# SENSORS_FMU3_REV_G.net
KiCad netlist of a schematic drawn in Altium Designer
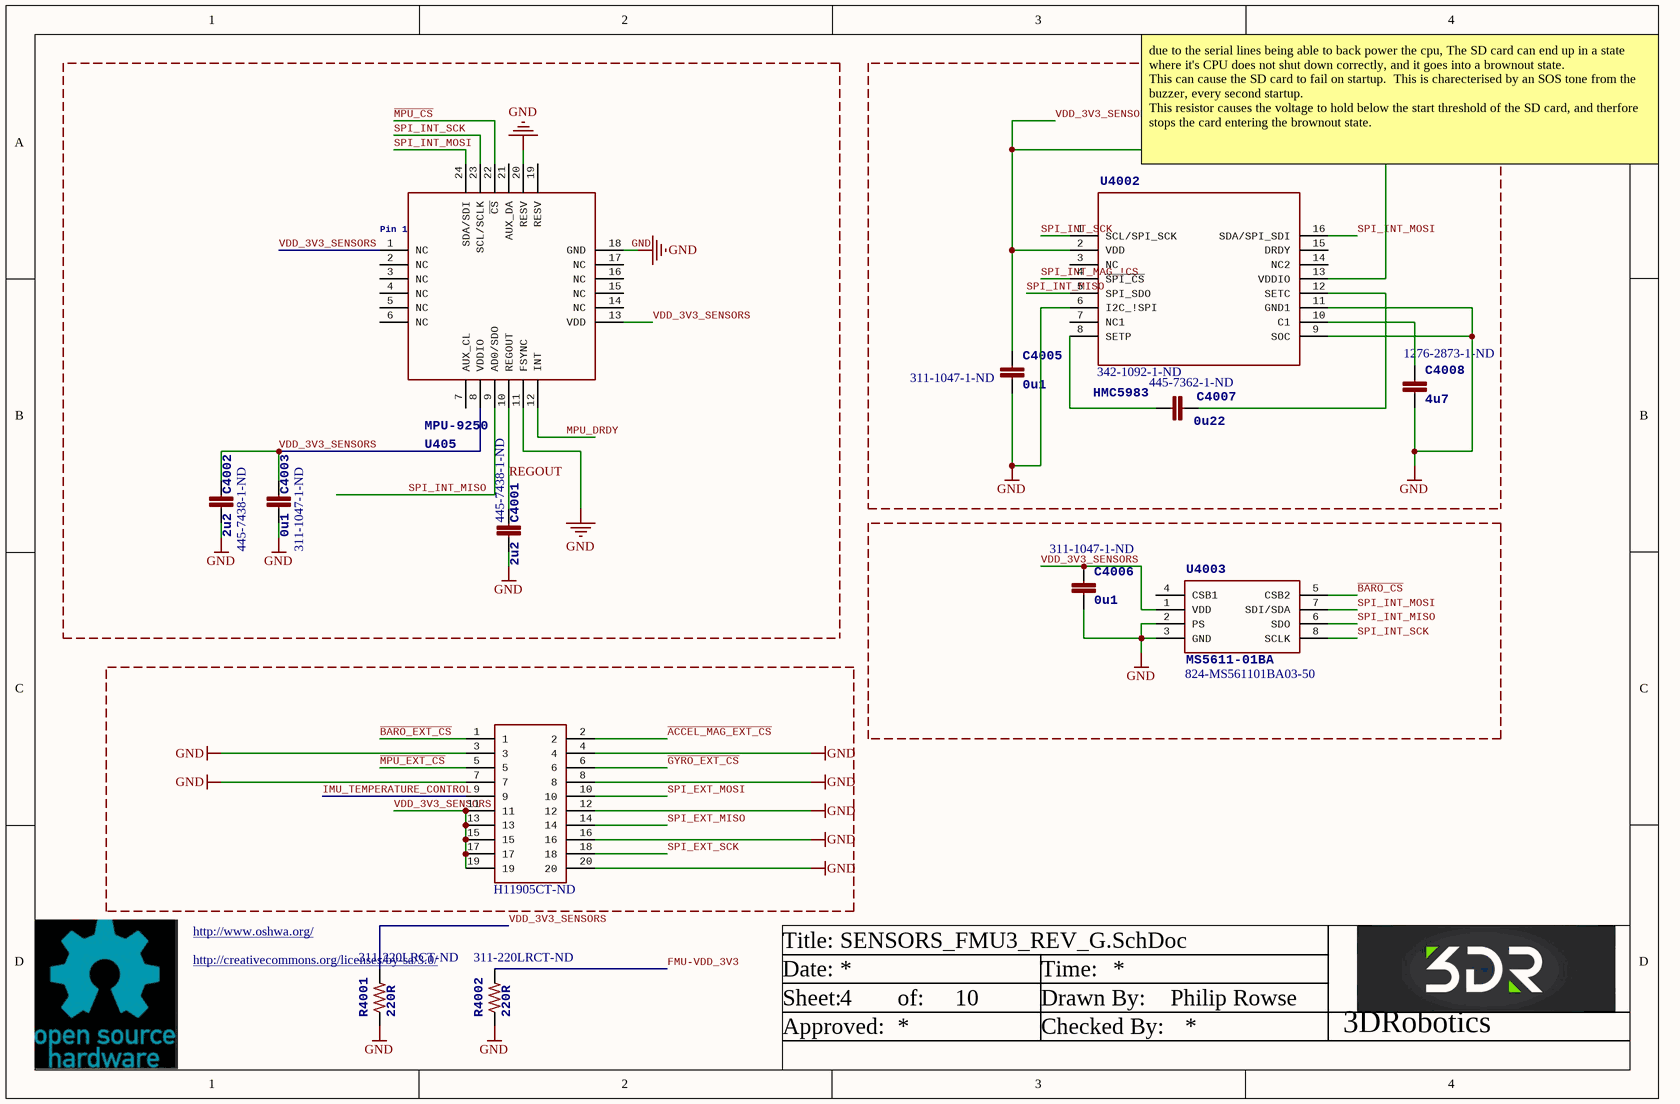
[diagram p0: SENSORS_FMU3_REV_G.SchDoc]

(export (version "E")
  (design (tool "Eeschema 10.0.6"))
  (components
    (comp (ref "C4001")
      (value "2u2")
      (footprint "0603-CAP")
      (description "CAP CER 2.2UF 16V 10% X6S 0603")
      (fields
        (field (name "PARTNO") "C1608X6S1C225K080AC")
        (field (name "SUPPLIER PART NUMBER 1") "445-7438-1-ND")
        (field (name "3DR_PARTNO") "ECM0619")
      )
      (libsource (lib "pixhawk2") (part "CAP0603"))
    )
    (comp (ref "C4002")
      (value "2u2")
      (footprint "0603-CAP")
      (description "CAP CER 2.2UF 16V 10% X6S 0603")
      (fields
        (field (name "PARTNO") "C1608X6S1C225K080AC")
        (field (name "SUPPLIER PART NUMBER 1") "445-7438-1-ND")
        (field (name "3DR_PARTNO") "ECM0619")
      )
      (libsource (lib "pixhawk2") (part "CAP0603"))
    )
    (comp (ref "C4003")
      (value "0u1")
      (footprint "0402-CAP")
      (description "CAP CER 0.1UF 16V Y5V 0402")
      (fields
        (field (name "PARTNO") "CC0402ZRY5V7BB104")
        (field (name "SUPPLIER PART NUMBER 1") "311-1047-1-ND")
        (field (name "3DR_PARTNO") "ECM0700")
      )
      (libsource (lib "pixhawk2") (part "CAP0402"))
    )
    (comp (ref "C4005")
      (value "0u1")
      (footprint "0402-CAP")
      (description "CAP CER 0.1UF 16V Y5V 0402")
      (fields
        (field (name "SUPPLIER PART NUMBER 1") "311-1047-1-ND")
        (field (name "3DR_PARTNO") "ECM0700")
        (field (name "PARTNO") "CC0402ZRY5V7BB104")
      )
      (libsource (lib "pixhawk2") (part "CAP0402"))
    )
    (comp (ref "C4006")
      (value "0u1")
      (footprint "0402-CAP")
      (description "CAP CER 0.1UF 16V Y5V 0402")
      (fields
        (field (name "PARTNO") "CC0402ZRY5V7BB104")
        (field (name "SUPPLIER PART NUMBER 1") "311-1047-1-ND")
        (field (name "3DR_PARTNO") "ECM0700")
      )
      (libsource (lib "pixhawk2") (part "CAP0402"))
    )
    (comp (ref "C4007")
      (value "0u22")
      (footprint "0402-CAP")
      (description "CAP CER 0.22UF 25V 10% X7R 0402")
      (fields
        (field (name "3DR_PARTNO") "ECM")
        (field (name "PARTNO") "C1005X6S1E224K050BC")
        (field (name "SUPPLIER PART NUMBER 1") "445-7362-1-ND")
      )
      (libsource (lib "") (part "CAP0402_1"))
    )
    (comp (ref "C4008")
      (value "4u7")
      (footprint "0805")
      (description "CAP CER 4.7UF 16V 10% X7R 0805")
      (fields
        (field (name "PARTNO") "CL21B475KOFNNNE")
        (field (name "SUPPLIER PART NUMBER 1") "1276-2873-1-ND")
        (field (name "3DR_PARTNO") "ECM0622")
      )
      (libsource (lib "pixhawk2") (part "CAP0805"))
    )
    (comp (ref "R4001")
      (value "220R")
      (footprint "0402-RES")
      (description "RES 220 OHM 1/16W 1% 0402 SMD")
      (fields
        (field (name "SUPPLIER PART NUMBER 1") "311-220LRCT-ND")
        (field (name "3DR_PARTNO") "ECM0821")
        (field (name "PARTNO") "RC0402FR-07220RL")
      )
      (libsource (lib "pixhawk2") (part "RESISTOR0402-RES"))
    )
    (comp (ref "R4002")
      (value "220R")
      (footprint "0402-RES")
      (description "RES 220 OHM 1/16W 1% 0402 SMD")
      (fields
        (field (name "SUPPLIER PART NUMBER 1") "311-220LRCT-ND")
        (field (name "3DR_PARTNO") "ECM0821")
        (field (name "PARTNO") "RC0402FR-07220RL")
      )
      (libsource (lib "pixhawk2") (part "RESISTOR0402-RES"))
    )
    (comp (ref "U$2")
      (value "DF40C-20-DS")
      (footprint "DF-40C-20DS")
      (description "CONN RCPT 20POS 0.4MM SMD GOLD")
      (fields
        (field (name "SUPPLIER PART NUMBER 1") "H11905CT-ND")
        (field (name "3DR_PARTNO") "ECM0517")
        (field (name "PARTNO") "DF40C(2.0)-20DS-0.4V(51)")
      )
      (libsource (lib "pixhawk2") (part "DF40C-20-DS"))
    )
    (comp (ref "U405")
      (value "MPU-9250")
      (footprint "MPU-9250")
      (fields (field (name "PIN 1") "Pin 1"))
      (libsource (lib "pixhawk2") (part "MPU-6500"))
    )
    (comp (ref "U4002")
      (value "HMC5983")
      (footprint "HMC5983-new")
      (description "IC COMPASS 3 AXIS 16-LCC")
      (fields (field (name "SUPPLIER PART NUMBER 1") "342-1092-1-ND") (field (name "3DR_PARTNO") "ECM0672"))
      (libsource (lib "pixhawk2") (part "HMC5983"))
    )
    (comp (ref "U4003")
      (value "MS5611-01BA")
      (footprint "MS5611-01BA")
      (description "Board Mount Pressure Sensors")
      (fields
        (field (name "SUPPLIER PART NUMBER 1") "824-MS561101BA03-50")
        (field (name "3DR_PARTNO") "ECM0835")
      )
      (libsource (lib "pixhawk2") (part "MS5611-01BA"))
    )
  )
  (nets
    (net (code "1") (name "/FMU-VDD_3V3") (class "Default")
      (node (ref "R4002") (pin "P$2") (pinfunction "2_P$2") (pintype "passive"))
    )
    (net (code "2") (name "/IMU_TEMPERATURE_CONTROL") (class "Default")
      (node (ref "U$2") (pin "9") (pinfunction "9_9") (pintype "passive"))
    )
    (net (code "3") (name "/MPU_DRDY") (class "Default")
      (node (ref "U405") (pin "12") (pinfunction "INT_12") (pintype "passive"))
    )
    (net (code "4") (name "/REGOUT") (class "Default")
      (node (ref "C4001") (pin "P$1") (pinfunction "1_P$1") (pintype "passive"))
      (node (ref "U405") (pin "10") (pinfunction "REGOUT_10") (pintype "passive"))
    )
    (net (code "5") (name "/SPI_EXT_MISO") (class "Default")
      (node (ref "U$2") (pin "14") (pinfunction "14_14") (pintype "passive"))
    )
    (net (code "6") (name "/SPI_EXT_MOSI") (class "Default")
      (node (ref "U$2") (pin "10") (pinfunction "10_10") (pintype "passive"))
    )
    (net (code "7") (name "/SPI_EXT_SCK") (class "Default")
      (node (ref "U$2") (pin "18") (pinfunction "18_18") (pintype "passive"))
    )
    (net (code "8") (name "/SPI_INT_MAG_!CS") (class "Default")
      (node (ref "U4002") (pin "4") (pinfunction "~{SPI_CS}_4") (pintype "passive"))
    )
    (net (code "9") (name "/SPI_INT_MISO") (class "Default")
      (node (ref "U4002") (pin "5") (pinfunction "SPI_SDO_5") (pintype "passive"))
      (node (ref "U4003") (pin "6") (pinfunction "SDO_6") (pintype "passive"))
      (node (ref "U405") (pin "9") (pinfunction "AD0/SDO_9") (pintype "passive"))
    )
    (net (code "10") (name "/SPI_INT_MOSI") (class "Default")
      (node (ref "U4002") (pin "16") (pinfunction "SDA/SPI_SDI_16") (pintype "passive"))
      (node (ref "U4003") (pin "7") (pinfunction "SDI/SDA_7") (pintype "passive"))
      (node (ref "U405") (pin "24") (pinfunction "SDA/SDI_24") (pintype "passive"))
    )
    (net (code "11") (name "/SPI_INT_SCK") (class "Default")
      (node (ref "U4002") (pin "1") (pinfunction "SCL/SPI_SCK_1") (pintype "passive"))
      (node (ref "U4003") (pin "8") (pinfunction "SCLK_8") (pintype "passive"))
      (node (ref "U405") (pin "23") (pinfunction "SCL/SCLK_23") (pintype "passive"))
    )
    (net (code "12") (name "/VDD_3V3_SENSORS") (class "Default")
      (node (ref "C4002") (pin "P$1") (pinfunction "1_P$1") (pintype "passive"))
      (node (ref "C4003") (pin "P$1") (pinfunction "1_P$1") (pintype "passive"))
      (node (ref "C4005") (pin "P$1") (pinfunction "1_P$1") (pintype "passive"))
      (node (ref "C4006") (pin "P$1") (pinfunction "1_P$1") (pintype "passive"))
      (node (ref "R4001") (pin "P$2") (pinfunction "2_P$2") (pintype "passive"))
      (node (ref "U$2") (pin "11") (pinfunction "11_11") (pintype "passive"))
      (node (ref "U$2") (pin "13") (pinfunction "13_13") (pintype "passive"))
      (node (ref "U$2") (pin "15") (pinfunction "15_15") (pintype "passive"))
      (node (ref "U$2") (pin "17") (pinfunction "17_17") (pintype "passive"))
      (node (ref "U$2") (pin "19") (pinfunction "19_19") (pintype "passive"))
      (node (ref "U4002") (pin "13") (pinfunction "VDDIO_13") (pintype "power_in"))
      (node (ref "U4002") (pin "2") (pinfunction "VDD_2") (pintype "power_in"))
      (node (ref "U4003") (pin "1") (pinfunction "VDD_1") (pintype "passive"))
      (node (ref "U405") (pin "1") (pinfunction "NC_1") (pintype "passive"))
      (node (ref "U405") (pin "13") (pinfunction "VDD_13") (pintype "passive"))
      (node (ref "U405") (pin "8") (pinfunction "VDDIO_8") (pintype "passive"))
    )
    (net (code "13") (name "/~{ACCEL_MAG_EXT_CS}") (class "Default")
      (node (ref "U$2") (pin "2") (pinfunction "2_2") (pintype "passive"))
    )
    (net (code "14") (name "/~{BARO_CS}") (class "Default")
      (node (ref "U4003") (pin "5") (pinfunction "CSB2_5") (pintype "passive"))
    )
    (net (code "15") (name "/~{BARO_EXT_CS}") (class "Default")
      (node (ref "U$2") (pin "1") (pinfunction "1_1") (pintype "passive"))
    )
    (net (code "16") (name "/~{GYRO_EXT_CS}") (class "Default")
      (node (ref "U$2") (pin "6") (pinfunction "6_6") (pintype "passive"))
    )
    (net (code "17") (name "/~{MPU_CS}") (class "Default")
      (node (ref "U405") (pin "22") (pinfunction "~{CS}_22") (pintype "passive"))
    )
    (net (code "18") (name "/~{MPU_EXT_CS}") (class "Default")
      (node (ref "U$2") (pin "5") (pinfunction "5_5") (pintype "passive"))
    )
    (net (code "19") (name "GND") (class "Default")
      (node (ref "C4001") (pin "P$2") (pinfunction "2_P$2") (pintype "passive"))
      (node (ref "C4002") (pin "P$2") (pinfunction "2_P$2") (pintype "passive"))
      (node (ref "C4003") (pin "P$2") (pinfunction "2_P$2") (pintype "passive"))
      (node (ref "C4005") (pin "P$2") (pinfunction "2_P$2") (pintype "passive"))
      (node (ref "C4006") (pin "P$2") (pinfunction "2_P$2") (pintype "passive"))
      (node (ref "C4008") (pin "2") (pinfunction "2_2") (pintype "passive"))
      (node (ref "R4001") (pin "P$1") (pinfunction "1_P$1") (pintype "passive"))
      (node (ref "R4002") (pin "P$1") (pinfunction "1_P$1") (pintype "passive"))
      (node (ref "U$2") (pin "12") (pinfunction "12_12") (pintype "passive"))
      (node (ref "U$2") (pin "16") (pinfunction "16_16") (pintype "passive"))
      (node (ref "U$2") (pin "20") (pinfunction "20_20") (pintype "passive"))
      (node (ref "U$2") (pin "3") (pinfunction "3_3") (pintype "passive"))
      (node (ref "U$2") (pin "4") (pinfunction "4_4") (pintype "passive"))
      (node (ref "U$2") (pin "7") (pinfunction "7_7") (pintype "passive"))
      (node (ref "U$2") (pin "8") (pinfunction "8_8") (pintype "passive"))
      (node (ref "U4002") (pin "11") (pinfunction "GND1_11") (pintype "passive"))
      (node (ref "U4002") (pin "6") (pinfunction "I2C_!SPI_6") (pintype "passive"))
      (node (ref "U4002") (pin "9") (pinfunction "SOC_9") (pintype "passive"))
      (node (ref "U4003") (pin "2") (pinfunction "PS_2") (pintype "passive"))
      (node (ref "U4003") (pin "3") (pinfunction "GND_3") (pintype "passive"))
      (node (ref "U405") (pin "11") (pinfunction "FSYNC_11") (pintype "passive"))
      (node (ref "U405") (pin "18") (pinfunction "GND_18") (pintype "passive"))
      (node (ref "U405") (pin "20") (pinfunction "RESV_20") (pintype "passive"))
    )
    (net (code "20") (name "Net-(C4007-1)") (class "Default")
      (node (ref "C4007") (pin "P$1") (pinfunction "1_P$1") (pintype "passive"))
      (node (ref "U4002") (pin "12") (pinfunction "SETC_12") (pintype "passive"))
    )
    (net (code "21") (name "Net-(C4007-2)") (class "Default")
      (node (ref "C4007") (pin "P$2") (pinfunction "2_P$2") (pintype "passive"))
      (node (ref "U4002") (pin "8") (pinfunction "SETP_8") (pintype "passive"))
    )
    (net (code "22") (name "Net-(U4002-C1)") (class "Default")
      (node (ref "C4008") (pin "1") (pinfunction "1_1") (pintype "passive"))
      (node (ref "U4002") (pin "10") (pinfunction "C1_10") (pintype "passive"))
    )
    (net (code "23") (name "unconnected-(U405-AUX_CL-Pad7)") (class "Default")
      (node (ref "U405") (pin "7") (pinfunction "AUX_CL_7") (pintype "passive"))
    )
    (net (code "24") (name "unconnected-(U405-AUX_DA-Pad21)") (class "Default")
      (node (ref "U405") (pin "21") (pinfunction "AUX_DA_21") (pintype "passive"))
    )
    (net (code "25") (name "unconnected-(U405-NC-Pad2)") (class "Default")
      (node (ref "U405") (pin "2") (pinfunction "NC_2") (pintype "passive"))
    )
    (net (code "26") (name "unconnected-(U405-NC-Pad3)") (class "Default")
      (node (ref "U405") (pin "3") (pinfunction "NC_3") (pintype "passive"))
    )
    (net (code "27") (name "unconnected-(U405-NC-Pad4)") (class "Default")
      (node (ref "U405") (pin "4") (pinfunction "NC_4") (pintype "passive"))
    )
    (net (code "28") (name "unconnected-(U405-NC-Pad5)") (class "Default")
      (node (ref "U405") (pin "5") (pinfunction "NC_5") (pintype "passive"))
    )
    (net (code "29") (name "unconnected-(U405-NC-Pad6)") (class "Default")
      (node (ref "U405") (pin "6") (pinfunction "NC_6") (pintype "passive"))
    )
    (net (code "30") (name "unconnected-(U405-NC-Pad14)") (class "Default")
      (node (ref "U405") (pin "14") (pinfunction "NC_14") (pintype "passive"))
    )
    (net (code "31") (name "unconnected-(U405-NC-Pad15)") (class "Default")
      (node (ref "U405") (pin "15") (pinfunction "NC_15") (pintype "passive"))
    )
    (net (code "32") (name "unconnected-(U405-NC-Pad16)") (class "Default")
      (node (ref "U405") (pin "16") (pinfunction "NC_16") (pintype "passive"))
    )
    (net (code "33") (name "unconnected-(U405-NC-Pad17)") (class "Default")
      (node (ref "U405") (pin "17") (pinfunction "NC_17") (pintype "passive"))
    )
    (net (code "34") (name "unconnected-(U405-RESV-Pad19)") (class "Default")
      (node (ref "U405") (pin "19") (pinfunction "RESV_19") (pintype "passive"))
    )
    (net (code "35") (name "unconnected-(U4002-DRDY-Pad15)") (class "Default")
      (node (ref "U4002") (pin "15") (pinfunction "DRDY_15") (pintype "passive"))
    )
    (net (code "36") (name "unconnected-(U4002-NC-Pad3)") (class "Default")
      (node (ref "U4002") (pin "3") (pinfunction "NC_3") (pintype "passive"))
    )
    (net (code "37") (name "unconnected-(U4002-NC1-Pad7)") (class "Default")
      (node (ref "U4002") (pin "7") (pinfunction "NC1_7") (pintype "passive"))
    )
    (net (code "38") (name "unconnected-(U4002-NC2-Pad14)") (class "Default")
      (node (ref "U4002") (pin "14") (pinfunction "NC2_14") (pintype "passive"))
    )
    (net (code "39") (name "unconnected-(U4003-CSB1-Pad4)") (class "Default")
      (node (ref "U4003") (pin "4") (pinfunction "CSB1_4") (pintype "passive"))
    )
  )
)
